# Proiect_TSC_v102.net
KiCad netlist of a schematic drawn in EAGLE
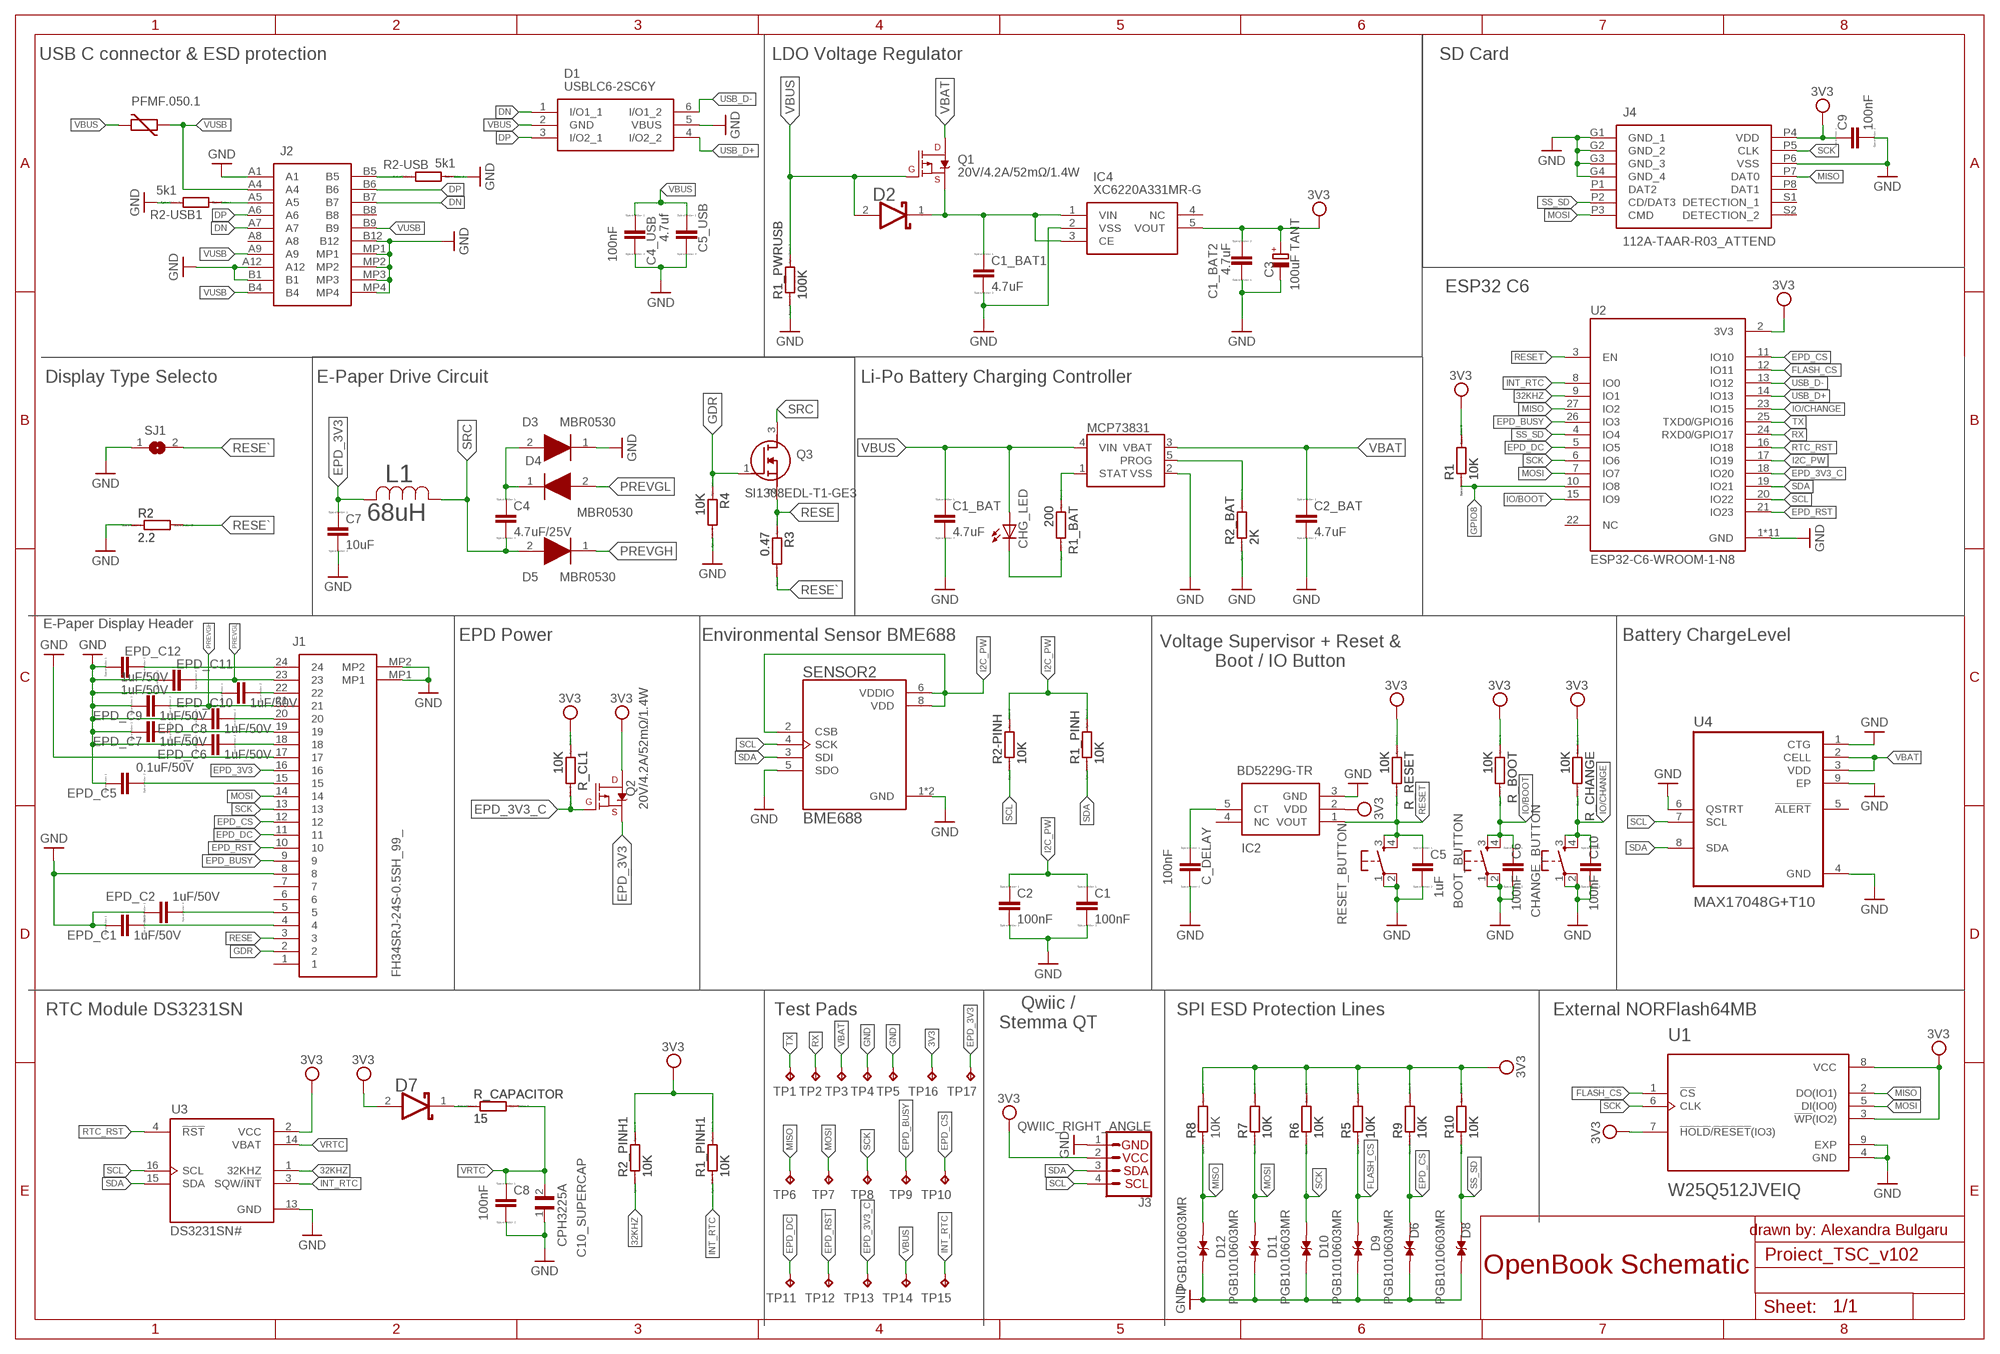
[diagram p0: schematic, sheet 1]

(export (version "E")
  (design (tool "Eeschema 10.0.6"))
  (components
    (comp (ref "BOOT_BUTTON")
      (value "BUTTON_CUSYOMV1")
      (footprint "eagle-import:MYBUTTON")
      (libsource (lib "eagle-import") (part "BUTTON_CUSYOMV1"))
    )
    (comp (ref "C1")
      (value "100nF")
      (footprint "eagle-import:EAGLE-LTSPICE_C0402")
      (libsource (lib "eagle-import") (part "EAGLE-LTSPICE_CC0402"))
    )
    (comp (ref "C1_BAT")
      (value "4.7uF")
      (footprint "eagle-import:EAGLE-LTSPICE_C0402")
      (libsource (lib "eagle-import") (part "EAGLE-LTSPICE_CC0402"))
    )
    (comp (ref "C1_BAT1")
      (value "4.7uF")
      (footprint "eagle-import:EAGLE-LTSPICE_C0402")
      (libsource (lib "eagle-import") (part "EAGLE-LTSPICE_CC0402"))
    )
    (comp (ref "C1_BAT2")
      (value "4.7uF")
      (footprint "eagle-import:EAGLE-LTSPICE_C0402")
      (libsource (lib "eagle-import") (part "EAGLE-LTSPICE_CC0402"))
    )
    (comp (ref "C2")
      (value "100nF")
      (footprint "eagle-import:EAGLE-LTSPICE_C0402")
      (libsource (lib "eagle-import") (part "EAGLE-LTSPICE_CC0402"))
    )
    (comp (ref "C2_BAT")
      (value "4.7uF")
      (footprint "eagle-import:EAGLE-LTSPICE_C0402")
      (libsource (lib "eagle-import") (part "EAGLE-LTSPICE_CC0402"))
    )
    (comp (ref "C3")
      (value "100uF TANT")
      (footprint "eagle-import:RCL_CT3528")
      (libsource (lib "eagle-import") (part "RCL_CPOL-EUCT3528"))
    )
    (comp (ref "C4")
      (value "4.7uF/25V")
      (footprint "eagle-import:EAGLE-LTSPICE_C0402")
      (libsource (lib "eagle-import") (part "EAGLE-LTSPICE_CC0402"))
    )
    (comp (ref "C4_USB")
      (value "100nF")
      (footprint "eagle-import:EAGLE-LTSPICE_C0402")
      (libsource (lib "eagle-import") (part "EAGLE-LTSPICE_CC0402"))
    )
    (comp (ref "C5")
      (value "1uF")
      (footprint "eagle-import:EAGLE-LTSPICE_C0402")
      (libsource (lib "eagle-import") (part "EAGLE-LTSPICE_CC0402"))
    )
    (comp (ref "C5_USB")
      (value "4.7uf")
      (footprint "eagle-import:EAGLE-LTSPICE_C0402")
      (libsource (lib "eagle-import") (part "EAGLE-LTSPICE_CC0402"))
    )
    (comp (ref "C6")
      (value "100nF")
      (footprint "eagle-import:EAGLE-LTSPICE_C0402")
      (libsource (lib "eagle-import") (part "EAGLE-LTSPICE_CC0402"))
    )
    (comp (ref "C7")
      (value "10uF")
      (footprint "eagle-import:EAGLE-LTSPICE_C0402")
      (libsource (lib "eagle-import") (part "EAGLE-LTSPICE_CC0402"))
    )
    (comp (ref "C8")
      (value "100nF")
      (footprint "eagle-import:EAGLE-LTSPICE_C0402")
      (libsource (lib "eagle-import") (part "EAGLE-LTSPICE_CC0402"))
    )
    (comp (ref "C9")
      (value "100nF")
      (footprint "eagle-import:ESP32_WROVER_EAGLE-LTSPICE_C0402")
      (libsource (lib "eagle-import") (part "ESP32_WROVER_EAGLE-LTSPICE_CC0402"))
    )
    (comp (ref "C10")
      (value "100nF")
      (footprint "eagle-import:EAGLE-LTSPICE_C0402")
      (libsource (lib "eagle-import") (part "EAGLE-LTSPICE_CC0402"))
    )
    (comp (ref "C10_SUPERCAP")
      (value "CPH3225A")
      (footprint "eagle-import:CAPCP3225X100N")
      (fields (field (name "MF") "Seiko Instruments"))
      (libsource (lib "eagle-import") (part "CPH3225A"))
    )
    (comp (ref "CHANGE_BUTTON")
      (value "BUTTON_CUSYOMV1")
      (footprint "eagle-import:MYBUTTON")
      (libsource (lib "eagle-import") (part "BUTTON_CUSYOMV1"))
    )
    (comp (ref "CHG_LED")
      (value "ADAFRUIT_LEDCHIP-LED0603")
      (footprint "eagle-import:ADAFRUIT_CHIP-LED0603")
      (libsource (lib "eagle-import") (part "ADAFRUIT_LEDCHIP-LED0603"))
    )
    (comp (ref "C_DELAY")
      (value "100nF")
      (footprint "eagle-import:EAGLE-LTSPICE_C0402")
      (libsource (lib "eagle-import") (part "EAGLE-LTSPICE_CC0402"))
    )
    (comp (ref "D1")
      (value "USBLC6-2SC6Y")
      (footprint "eagle-import:SOT95P280X145-6N")
      (fields (field (name "MF") "STMicroelectronics"))
      (libsource (lib "eagle-import") (part "USBLC6-2SC6Y"))
    )
    (comp (ref "D2")
      (value "ESP32_WROVER_AVX---SD0805S020S1R0_AVX_SD0805S020S1R0_0_0AVX_SD0805S020S1R0_0_0")
      (footprint "eagle-import:ESP32_WROVER_AVX---SD0805S020S1R0_AVX_SD0805S020S1R0_0")
      (fields
        (field (name "DIGIKEY_PART_NUMBER") "478-7800-1-ND")
        (field (name "MF") "AVX")
        (field (name "MOUSER_PART_NUMBER") "581-SD0805S020S1R0")
      )
      (libsource (lib "eagle-import") (part "ESP32_WROVER_AVX---SD0805S020S1R0_AVX_SD0805S020S1R0_0_0AVX_SD0805S020S1R0_0_0"))
    )
    (comp (ref "D3")
      (value "MBR0530")
      (footprint "eagle-import:SOD3716X135N")
      (fields (field (name "MF") "ON Semiconductor"))
      (libsource (lib "eagle-import") (part "MBR0530"))
    )
    (comp (ref "D4")
      (value "MBR0530")
      (footprint "eagle-import:SOD3716X135N")
      (fields (field (name "MF") "ON Semiconductor"))
      (libsource (lib "eagle-import") (part "MBR0530"))
    )
    (comp (ref "D5")
      (value "MBR0530")
      (footprint "eagle-import:SOD3716X135N")
      (fields (field (name "MF") "ON Semiconductor"))
      (libsource (lib "eagle-import") (part "MBR0530"))
    )
    (comp (ref "D6")
      (value "PGB1010603MR")
      (footprint "eagle-import:DIOC1608X36N")
      (fields (field (name "MF") "Littelfuse Inc."))
      (libsource (lib "eagle-import") (part "PGB1010603MR"))
    )
    (comp (ref "D7")
      (value "ESP32_WROVER_AVX---SD0805S020S1R0_AVX_SD0805S020S1R0_0_0AVX_SD0805S020S1R0_0_0")
      (footprint "eagle-import:ESP32_WROVER_AVX---SD0805S020S1R0_AVX_SD0805S020S1R0_0")
      (fields
        (field (name "DIGIKEY_PART_NUMBER") "478-7800-1-ND")
        (field (name "MF") "AVX")
        (field (name "MOUSER_PART_NUMBER") "581-SD0805S020S1R0")
      )
      (libsource (lib "eagle-import") (part "ESP32_WROVER_AVX---SD0805S020S1R0_AVX_SD0805S020S1R0_0_0AVX_SD0805S020S1R0_0_0"))
    )
    (comp (ref "D8")
      (value "PGB1010603MR")
      (footprint "eagle-import:DIOC1608X36N")
      (fields (field (name "MF") "Littelfuse Inc."))
      (libsource (lib "eagle-import") (part "PGB1010603MR"))
    )
    (comp (ref "D9")
      (value "PGB1010603MR")
      (footprint "eagle-import:DIOC1608X36N")
      (fields (field (name "MF") "Littelfuse Inc."))
      (libsource (lib "eagle-import") (part "PGB1010603MR"))
    )
    (comp (ref "D10")
      (value "PGB1010603MR")
      (footprint "eagle-import:DIOC1608X36N")
      (fields (field (name "MF") "Littelfuse Inc."))
      (libsource (lib "eagle-import") (part "PGB1010603MR"))
    )
    (comp (ref "D11")
      (value "PGB1010603MR")
      (footprint "eagle-import:DIOC1608X36N")
      (fields (field (name "MF") "Littelfuse Inc."))
      (libsource (lib "eagle-import") (part "PGB1010603MR"))
    )
    (comp (ref "D12")
      (value "PGB1010603MR")
      (footprint "eagle-import:DIOC1608X36N")
      (fields (field (name "MF") "Littelfuse Inc."))
      (libsource (lib "eagle-import") (part "PGB1010603MR"))
    )
    (comp (ref "EPD_C1")
      (value "1uF/50V")
      (footprint "eagle-import:EAGLE-LTSPICE_C0402")
      (libsource (lib "eagle-import") (part "EAGLE-LTSPICE_CC0402"))
    )
    (comp (ref "EPD_C2")
      (value "1uF/50V")
      (footprint "eagle-import:EAGLE-LTSPICE_C0402")
      (libsource (lib "eagle-import") (part "EAGLE-LTSPICE_CC0402"))
    )
    (comp (ref "EPD_C5")
      (value "0.1uF/50V")
      (footprint "eagle-import:EAGLE-LTSPICE_C0402")
      (libsource (lib "eagle-import") (part "EAGLE-LTSPICE_CC0402"))
    )
    (comp (ref "EPD_C6")
      (value "1uF/50V")
      (footprint "eagle-import:EAGLE-LTSPICE_C0402")
      (libsource (lib "eagle-import") (part "EAGLE-LTSPICE_CC0402"))
    )
    (comp (ref "EPD_C7")
      (value "1uF/50V")
      (footprint "eagle-import:EAGLE-LTSPICE_C0402")
      (libsource (lib "eagle-import") (part "EAGLE-LTSPICE_CC0402"))
    )
    (comp (ref "EPD_C8")
      (value "1uF/50V")
      (footprint "eagle-import:EAGLE-LTSPICE_C0402")
      (libsource (lib "eagle-import") (part "EAGLE-LTSPICE_CC0402"))
    )
    (comp (ref "EPD_C9")
      (value "1uF/50V")
      (footprint "eagle-import:EAGLE-LTSPICE_C0402")
      (libsource (lib "eagle-import") (part "EAGLE-LTSPICE_CC0402"))
    )
    (comp (ref "EPD_C10")
      (value "1uF/50V")
      (footprint "eagle-import:EAGLE-LTSPICE_C0402")
      (libsource (lib "eagle-import") (part "EAGLE-LTSPICE_CC0402"))
    )
    (comp (ref "EPD_C11")
      (value "1uF/50V")
      (footprint "eagle-import:EAGLE-LTSPICE_C0402")
      (libsource (lib "eagle-import") (part "EAGLE-LTSPICE_CC0402"))
    )
    (comp (ref "EPD_C12")
      (value "1uF/50V")
      (footprint "eagle-import:EAGLE-LTSPICE_C0402")
      (libsource (lib "eagle-import") (part "EAGLE-LTSPICE_CC0402"))
    )
    (comp (ref "IC2")
      (value "BD5229G-TR")
      (footprint "eagle-import:SOT95P280X125-5N")
      (fields (field (name "MOUSER_PART_NUMBER") "755-BD5229G-TR"))
      (libsource (lib "eagle-import") (part "BD5229G-TR"))
    )
    (comp (ref "IC4")
      (value "XC6220A331MR-G")
      (footprint "eagle-import:SOT95P280X120-5N")
      (fields (field (name "MOUSER_PART_NUMBER") "865-XC6220A331MR-G"))
      (libsource (lib "eagle-import") (part "XC6220A331MR-G"))
    )
    (comp (ref "J1")
      (value "FH34SRJ-24S-0.5SH_99_")
      (footprint "eagle-import:FH34SRJ24S05SH99")
      (fields
        (field (name "MANUFACTURER_PART_NUMBER") "FH34SRJ-24S-0.5SH(99)")
        (field (name "MOUSER_PART_NUMBER") "798-FH34SRJ24S05SH99")
      )
      (libsource (lib "eagle-import") (part "FH34SRJ-24S-0.5SH_99_"))
    )
    (comp (ref "J2")
      (value "SAMACSYS_PARTS_USB4110-GF-A")
      (footprint "eagle-import:SAMACSYS_PARTS_USB4110GFA")
      (fields
        (field (name "MANUFACTURER_PART_NUMBER") "USB4110-GF-A")
        (field (name "MOUSER_PART_NUMBER") "640-USB4110-GF-A")
      )
      (libsource (lib "eagle-import") (part "SAMACSYS_PARTS_USB4110-GF-A"))
    )
    (comp (ref "J3")
      (value "QWIIC_RIGHT_ANGLE")
      (footprint "eagle-import:JST04_1MM_RA")
      (libsource (lib "eagle-import") (part "QWIIC_CONNECTORJS-1MM"))
    )
    (comp (ref "J4")
      (value "112A-TAAR-R03_ATTEND")
      (footprint "eagle-import:112ATAARR03ATTEND")
      (fields (field (name "MANUFACTURER_PART_NUMBER") "112A-TAAR-R03 ATTEND"))
      (libsource (lib "eagle-import") (part "112A-TAAR-R03_ATTEND"))
    )
    (comp (ref "L1")
      (value "68uH")
      (footprint "eagle-import:IND_4828-WE-TPC_WRE")
      (fields
        (field (name "MANUFACTURER_PART_NUMBER") "744043680")
        (field (name "COPYRIGHT") "Copyright (C) 2024 Ultra Librarian. All rights reserved.")
      )
      (libsource (lib "eagle-import") (part "744043680IND_4828-WE-TPC_WRE"))
    )
    (comp (ref "MCP73831")
      (value "ESP32_WROVER_SPARKFUN-IC-POWER_MCP73831")
      (footprint "eagle-import:ESP32_WROVER_SPARKFUN-IC-POWER_SOT23-5")
      (libsource (lib "eagle-import") (part "ESP32_WROVER_SPARKFUN-IC-POWER_MCP73831"))
    )
    (comp (ref "PFMF.050.1")
      (value "ESP32C6_VARISTORCN1812")
      (footprint "eagle-import:ESP32C6_VARISTOR_CT_CN1812")
      (libsource (lib "eagle-import") (part "ESP32C6_VARISTORCN1812"))
    )
    (comp (ref "Q1")
      (value "20V/4.2A/52mΩ/1.4W")
      (footprint "eagle-import:ESP32_WROVER_SPARKFUN-DISCRETESEMI_SOT23-3")
      (libsource (lib "eagle-import") (part "ESP32_WROVER_SPARKFUN-DISCRETESEMI_MOSFET_PCH-DMG2305UX-7"))
    )
    (comp (ref "Q2")
      (value "20V/4.2A/52mΩ/1.4W")
      (footprint "eagle-import:ESP32_WROVER_SPARKFUN-DISCRETESEMI_SOT23-3")
      (libsource (lib "eagle-import") (part "ESP32_WROVER_SPARKFUN-DISCRETESEMI_MOSFET_PCH-DMG2305UX-7"))
    )
    (comp (ref "Q3")
      (value "SI1308EDL-T1-GE3")
      (footprint "eagle-import:SOT65P210X110-3N")
      (fields (field (name "MF") "Vishay Siliconix"))
      (libsource (lib "eagle-import") (part "SI1308EDL-T1-GE3"))
    )
    (comp (ref "R1")
      (value "10K")
      (footprint "eagle-import:ESP32_WROVER_EAGLE-LTSPICE_R0402")
      (libsource (lib "eagle-import") (part "ESP32_WROVER_EAGLE-LTSPICE_RR0402"))
    )
    (comp (ref "R1_BAT")
      (value "200")
      (footprint "eagle-import:ESP32_WROVER_EAGLE-LTSPICE_R0402")
      (libsource (lib "eagle-import") (part "ESP32_WROVER_EAGLE-LTSPICE_RR0402"))
    )
    (comp (ref "R1_PINH")
      (value "10K")
      (footprint "eagle-import:ESP32_WROVER_EAGLE-LTSPICE_R0402")
      (libsource (lib "eagle-import") (part "ESP32_WROVER_EAGLE-LTSPICE_RR0402"))
    )
    (comp (ref "R1_PINH1")
      (value "10K")
      (footprint "eagle-import:ESP32_WROVER_EAGLE-LTSPICE_R0402")
      (libsource (lib "eagle-import") (part "ESP32_WROVER_EAGLE-LTSPICE_RR0402"))
    )
    (comp (ref "R1_PWRUSB")
      (value "100K")
      (footprint "eagle-import:ESP32_WROVER_EAGLE-LTSPICE_R0402")
      (libsource (lib "eagle-import") (part "ESP32_WROVER_EAGLE-LTSPICE_RR0402"))
    )
    (comp (ref "R2")
      (value "2.2")
      (footprint "eagle-import:ESP32_WROVER_EAGLE-LTSPICE_R0402")
      (libsource (lib "eagle-import") (part "ESP32_WROVER_EAGLE-LTSPICE_RR0402"))
    )
    (comp (ref "R2-PINH")
      (value "10K")
      (footprint "eagle-import:ESP32_WROVER_EAGLE-LTSPICE_R0402")
      (libsource (lib "eagle-import") (part "ESP32_WROVER_EAGLE-LTSPICE_RR0402"))
    )
    (comp (ref "R2-USB")
      (value "5k1")
      (footprint "eagle-import:ESP32_WROVER_EAGLE-LTSPICE_R0402")
      (libsource (lib "eagle-import") (part "ESP32_WROVER_EAGLE-LTSPICE_RR0402"))
    )
    (comp (ref "R2-USB1")
      (value "5k1")
      (footprint "eagle-import:ESP32_WROVER_EAGLE-LTSPICE_R0402")
      (libsource (lib "eagle-import") (part "ESP32_WROVER_EAGLE-LTSPICE_RR0402"))
    )
    (comp (ref "R2_BAT")
      (value "2K")
      (footprint "eagle-import:ESP32_WROVER_EAGLE-LTSPICE_R0402")
      (libsource (lib "eagle-import") (part "ESP32_WROVER_EAGLE-LTSPICE_RR0402"))
    )
    (comp (ref "R2_PINH1")
      (value "10K")
      (footprint "eagle-import:ESP32_WROVER_EAGLE-LTSPICE_R0402")
      (libsource (lib "eagle-import") (part "ESP32_WROVER_EAGLE-LTSPICE_RR0402"))
    )
    (comp (ref "R3")
      (value "0.47")
      (footprint "eagle-import:ESP32_WROVER_EAGLE-LTSPICE_R0402")
      (libsource (lib "eagle-import") (part "ESP32_WROVER_EAGLE-LTSPICE_RR0402"))
    )
    (comp (ref "R4")
      (value "10K")
      (footprint "eagle-import:ESP32_WROVER_EAGLE-LTSPICE_R0402")
      (libsource (lib "eagle-import") (part "ESP32_WROVER_EAGLE-LTSPICE_RR0402"))
    )
    (comp (ref "R5")
      (value "10K")
      (footprint "eagle-import:ESP32_WROVER_EAGLE-LTSPICE_R0402")
      (libsource (lib "eagle-import") (part "ESP32_WROVER_EAGLE-LTSPICE_RR0402"))
    )
    (comp (ref "R6")
      (value "10K")
      (footprint "eagle-import:ESP32_WROVER_EAGLE-LTSPICE_R0402")
      (libsource (lib "eagle-import") (part "ESP32_WROVER_EAGLE-LTSPICE_RR0402"))
    )
    (comp (ref "R7")
      (value "10K")
      (footprint "eagle-import:ESP32_WROVER_EAGLE-LTSPICE_R0402")
      (libsource (lib "eagle-import") (part "ESP32_WROVER_EAGLE-LTSPICE_RR0402"))
    )
    (comp (ref "R8")
      (value "10K")
      (footprint "eagle-import:ESP32_WROVER_EAGLE-LTSPICE_R0402")
      (libsource (lib "eagle-import") (part "ESP32_WROVER_EAGLE-LTSPICE_RR0402"))
    )
    (comp (ref "R9")
      (value "10K")
      (footprint "eagle-import:ESP32_WROVER_EAGLE-LTSPICE_R0402")
      (libsource (lib "eagle-import") (part "ESP32_WROVER_EAGLE-LTSPICE_RR0402"))
    )
    (comp (ref "R10")
      (value "10K")
      (footprint "eagle-import:ESP32_WROVER_EAGLE-LTSPICE_R0402")
      (libsource (lib "eagle-import") (part "ESP32_WROVER_EAGLE-LTSPICE_RR0402"))
    )
    (comp (ref "RESET_BUTTON")
      (value "BUTTON_CUSYOMV1")
      (footprint "eagle-import:MYBUTTON")
      (libsource (lib "eagle-import") (part "BUTTON_CUSYOMV1"))
    )
    (comp (ref "R_BOOT")
      (value "10K")
      (footprint "eagle-import:ESP32_WROVER_EAGLE-LTSPICE_R0402")
      (libsource (lib "eagle-import") (part "ESP32_WROVER_EAGLE-LTSPICE_RR0402"))
    )
    (comp (ref "R_CAPACITOR")
      (value "15")
      (footprint "eagle-import:ESP32_WROVER_EAGLE-LTSPICE_R0402")
      (libsource (lib "eagle-import") (part "ESP32_WROVER_EAGLE-LTSPICE_RR0402"))
    )
    (comp (ref "R_CHANGE")
      (value "10K")
      (footprint "eagle-import:ESP32_WROVER_EAGLE-LTSPICE_R0402")
      (libsource (lib "eagle-import") (part "ESP32_WROVER_EAGLE-LTSPICE_RR0402"))
    )
    (comp (ref "R_CL1")
      (value "10K")
      (footprint "eagle-import:ESP32_WROVER_EAGLE-LTSPICE_R0402")
      (libsource (lib "eagle-import") (part "ESP32_WROVER_EAGLE-LTSPICE_RR0402"))
    )
    (comp (ref "R_RESET")
      (value "10K")
      (footprint "eagle-import:ESP32_WROVER_EAGLE-LTSPICE_R0402")
      (libsource (lib "eagle-import") (part "ESP32_WROVER_EAGLE-LTSPICE_RR0402"))
    )
    (comp (ref "SENSOR2")
      (value "BME688")
      (footprint "eagle-import:ESP32_WROVER_BME680_PSON80P300X300X100-8N")
      (fields (field (name "MF") "Bosch Sensortec") (field (name "MP") "BME680"))
      (libsource (lib "eagle-import") (part "ESP32_WROVER_BME680_BME680"))
    )
    (comp (ref "SJ1") (value "SJ") (footprint "eagle-import:SJ") (libsource (lib "eagle-import") (part "SJ")))
    (comp (ref "TP1")
      (value "TPTP20R")
      (footprint "eagle-import:TP20R")
      (libsource (lib "eagle-import") (part "TPTP20R"))
    )
    (comp (ref "TP2")
      (value "TPTP20R")
      (footprint "eagle-import:TP20R")
      (libsource (lib "eagle-import") (part "TPTP20R"))
    )
    (comp (ref "TP3")
      (value "TPTP20R")
      (footprint "eagle-import:TP20R")
      (libsource (lib "eagle-import") (part "TPTP20R"))
    )
    (comp (ref "TP4")
      (value "TPTP20R")
      (footprint "eagle-import:TP20R")
      (libsource (lib "eagle-import") (part "TPTP20R"))
    )
    (comp (ref "TP5")
      (value "TPTP20R")
      (footprint "eagle-import:TP20R")
      (libsource (lib "eagle-import") (part "TPTP20R"))
    )
    (comp (ref "TP6")
      (value "TPTP20R")
      (footprint "eagle-import:TP20R")
      (libsource (lib "eagle-import") (part "TPTP20R"))
    )
    (comp (ref "TP7")
      (value "TPTP20R")
      (footprint "eagle-import:TP20R")
      (libsource (lib "eagle-import") (part "TPTP20R"))
    )
    (comp (ref "TP8")
      (value "TPTP20R")
      (footprint "eagle-import:TP20R")
      (libsource (lib "eagle-import") (part "TPTP20R"))
    )
    (comp (ref "TP9")
      (value "TPTP20R")
      (footprint "eagle-import:TP20R")
      (libsource (lib "eagle-import") (part "TPTP20R"))
    )
    (comp (ref "TP10")
      (value "TPTP20R")
      (footprint "eagle-import:TP20R")
      (libsource (lib "eagle-import") (part "TPTP20R"))
    )
    (comp (ref "TP11")
      (value "TPTP20R")
      (footprint "eagle-import:TP20R")
      (libsource (lib "eagle-import") (part "TPTP20R"))
    )
    (comp (ref "TP12")
      (value "TPTP20R")
      (footprint "eagle-import:TP20R")
      (libsource (lib "eagle-import") (part "TPTP20R"))
    )
    (comp (ref "TP13")
      (value "TPTP20R")
      (footprint "eagle-import:TP20R")
      (libsource (lib "eagle-import") (part "TPTP20R"))
    )
    (comp (ref "TP14")
      (value "TPTP20R")
      (footprint "eagle-import:TP20R")
      (libsource (lib "eagle-import") (part "TPTP20R"))
    )
    (comp (ref "TP15")
      (value "TPTP20R")
      (footprint "eagle-import:TP20R")
      (libsource (lib "eagle-import") (part "TPTP20R"))
    )
    (comp (ref "TP16")
      (value "TPTP20R")
      (footprint "eagle-import:TP20R")
      (libsource (lib "eagle-import") (part "TPTP20R"))
    )
    (comp (ref "TP17")
      (value "TPTP20R")
      (footprint "eagle-import:TP20R")
      (libsource (lib "eagle-import") (part "TPTP20R"))
    )
    (comp (ref "U1")
      (value "W25Q512JVEIQ")
      (footprint "eagle-import:SON127P600X800X80-9N")
      (fields (field (name "MF") "Winbond Electronics"))
      (libsource (lib "eagle-import") (part "W25Q512JVEIQ"))
    )
    (comp (ref "U2")
      (value "ESP32-C6-WROOM-1-N8")
      (footprint "eagle-import:XCVR_ESP32-C6-WROOM-1-N8")
      (fields (field (name "MF") "Espressif Systems"))
      (libsource (lib "eagle-import") (part "ESP32-C6-WROOM-1-N8"))
    )
    (comp (ref "U3")
      (value "DS3231SN#")
      (footprint "eagle-import:SOIC127P1032X265-16N")
      (fields (field (name "MF") "Analog Devices"))
      (libsource (lib "eagle-import") (part "DS3231SN#"))
    )
    (comp (ref "U4")
      (value "MAX17048G+T10")
      (footprint "eagle-import:SON50P200X200X80-9N")
      (fields (field (name "MF") "Analog Devices"))
      (libsource (lib "eagle-import") (part "MAX17048G+T10"))
    )
  )
  (nets
    (net (code "1") (name "3V3") (class "Default")
      (node (ref "C1_BAT2") (pin "2") (pinfunction "2_2") (pintype "passive"))
      (node (ref "C3") (pin "+") (pinfunction "+_+") (pintype "passive"))
      (node (ref "C9") (pin "1") (pinfunction "1_1") (pintype "passive"))
      (node (ref "D7") (pin "2") (pinfunction "ANODE_2") (pintype "bidirectional"))
      (node (ref "IC2") (pin "2") (pinfunction "VDD_2") (pintype "bidirectional"))
      (node (ref "IC4") (pin "5") (pinfunction "VOUT_5") (pintype "bidirectional"))
      (node (ref "J3") (pin "2") (pinfunction "2_2") (pintype "power_in"))
      (node (ref "J4") (pin "P4") (pinfunction "VDD_P4") (pintype "bidirectional"))
      (node (ref "Q2") (pin "3") (pinfunction "D_3") (pintype "bidirectional"))
      (node (ref "R1") (pin "2") (pinfunction "2_2") (pintype "passive"))
      (node (ref "R10") (pin "2") (pinfunction "2_2") (pintype "passive"))
      (node (ref "R1_PINH1") (pin "2") (pinfunction "2_2") (pintype "passive"))
      (node (ref "R2_PINH1") (pin "2") (pinfunction "2_2") (pintype "passive"))
      (node (ref "R5") (pin "2") (pinfunction "2_2") (pintype "passive"))
      (node (ref "R6") (pin "2") (pinfunction "2_2") (pintype "passive"))
      (node (ref "R7") (pin "2") (pinfunction "2_2") (pintype "passive"))
      (node (ref "R8") (pin "2") (pinfunction "2_2") (pintype "passive"))
      (node (ref "R9") (pin "2") (pinfunction "2_2") (pintype "passive"))
      (node (ref "R_BOOT") (pin "1") (pinfunction "1_1") (pintype "passive"))
      (node (ref "R_CHANGE") (pin "1") (pinfunction "1_1") (pintype "passive"))
      (node (ref "R_CL1") (pin "1") (pinfunction "1_1") (pintype "passive"))
      (node (ref "R_RESET") (pin "1") (pinfunction "1_1") (pintype "passive"))
      (node (ref "TP16") (pin "TP") (pinfunction "TP_TP") (pintype "input"))
      (node (ref "U1") (pin "3") (pinfunction "~{WP}(IO2)_3") (pintype "bidirectional"))
      (node (ref "U1") (pin "7") (pinfunction "~{HOLD}/~{RESET}(IO3)_7") (pintype "bidirectional"))
      (node (ref "U1") (pin "8") (pinfunction "VCC_8") (pintype "power_in"))
      (node (ref "U2") (pin "2") (pinfunction "3V3_2") (pintype "power_in"))
      (node (ref "U3") (pin "2") (pinfunction "VCC_2") (pintype "power_in"))
    )
    (net (code "2") (name "32KHZ") (class "Default")
      (node (ref "R2_PINH1") (pin "1") (pinfunction "1_1") (pintype "passive"))
      (node (ref "U2") (pin "9") (pinfunction "IO1_9") (pintype "bidirectional"))
      (node (ref "U3") (pin "1") (pinfunction "32KHZ_1") (pintype "output"))
    )
    (net (code "3") (name "DN") (class "Default")
      (node (ref "D1") (pin "1") (pinfunction "I/O1_1_1") (pintype "bidirectional"))
      (node (ref "J2") (pin "A7") (pinfunction "A7_A7") (pintype "bidirectional"))
      (node (ref "J2") (pin "B7") (pinfunction "B7_B7") (pintype "bidirectional"))
    )
    (net (code "4") (name "DP") (class "Default")
      (node (ref "D1") (pin "3") (pinfunction "I/O2_1_3") (pintype "bidirectional"))
      (node (ref "J2") (pin "A6") (pinfunction "A6_A6") (pintype "bidirectional"))
      (node (ref "J2") (pin "B6") (pinfunction "B6_B6") (pintype "bidirectional"))
    )
    (net (code "5") (name "EPD_3V3") (class "Default")
      (node (ref "C7") (pin "1") (pinfunction "1_1") (pintype "passive"))
      (node (ref "J1") (pin "16") (pinfunction "16_16") (pintype "bidirectional"))
      (node (ref "L1") (pin "2") (pinfunction "2_2") (pintype "passive"))
      (node (ref "Q2") (pin "2") (pinfunction "S_2") (pintype "bidirectional"))
      (node (ref "TP17") (pin "TP") (pinfunction "TP_TP") (pintype "input"))
    )
    (net (code "6") (name "EPD_3V3_C") (class "Default")
      (node (ref "Q2") (pin "1") (pinfunction "G_1") (pintype "bidirectional"))
      (node (ref "R_CL1") (pin "2") (pinfunction "2_2") (pintype "passive"))
      (node (ref "TP13") (pin "TP") (pinfunction "TP_TP") (pintype "input"))
      (node (ref "U2") (pin "18") (pinfunction "IO20_18") (pintype "bidirectional"))
    )
    (net (code "7") (name "EPD_BUSY") (class "Default")
      (node (ref "J1") (pin "9") (pinfunction "9_9") (pintype "bidirectional"))
      (node (ref "TP9") (pin "TP") (pinfunction "TP_TP") (pintype "input"))
      (node (ref "U2") (pin "26") (pinfunction "IO3_26") (pintype "bidirectional"))
    )
    (net (code "8") (name "EPD_CS") (class "Default")
      (node (ref "D6") (pin "1") (pinfunction "1_1") (pintype "passive"))
      (node (ref "J1") (pin "12") (pinfunction "12_12") (pintype "bidirectional"))
      (node (ref "R9") (pin "1") (pinfunction "1_1") (pintype "passive"))
      (node (ref "TP10") (pin "TP") (pinfunction "TP_TP") (pintype "input"))
      (node (ref "U2") (pin "11") (pinfunction "IO10_11") (pintype "bidirectional"))
    )
    (net (code "9") (name "EPD_DC") (class "Default")
      (node (ref "J1") (pin "11") (pinfunction "11_11") (pintype "bidirectional"))
      (node (ref "TP11") (pin "TP") (pinfunction "TP_TP") (pintype "input"))
      (node (ref "U2") (pin "5") (pinfunction "IO5_5") (pintype "bidirectional"))
    )
    (net (code "10") (name "EPD_RST") (class "Default")
      (node (ref "J1") (pin "10") (pinfunction "10_10") (pintype "bidirectional"))
      (node (ref "TP12") (pin "TP") (pinfunction "TP_TP") (pintype "input"))
      (node (ref "U2") (pin "21") (pinfunction "IO23_21") (pintype "bidirectional"))
    )
    (net (code "11") (name "FLASH_CS") (class "Default")
      (node (ref "D9") (pin "1") (pinfunction "1_1") (pintype "passive"))
      (node (ref "R5") (pin "1") (pinfunction "1_1") (pintype "passive"))
      (node (ref "U1") (pin "1") (pinfunction "~{CS}_1") (pintype "input"))
      (node (ref "U2") (pin "12") (pinfunction "IO11_12") (pintype "bidirectional"))
    )
    (net (code "12") (name "GDR") (class "Default")
      (node (ref "J1") (pin "2") (pinfunction "2_2") (pintype "bidirectional"))
      (node (ref "Q3") (pin "1") (pinfunction "G_1") (pintype "bidirectional"))
      (node (ref "R4") (pin "1") (pinfunction "1_1") (pintype "passive"))
    )
    (net (code "13") (name "GND") (class "Default")
      (node (ref "BOOT_BUTTON") (pin "1") (pinfunction "1_1") (pintype "passive"))
      (node (ref "BOOT_BUTTON") (pin "2") (pinfunction "2_2") (pintype "passive"))
      (node (ref "C1") (pin "2") (pinfunction "2_2") (pintype "passive"))
      (node (ref "C10") (pin "2") (pinfunction "2_2") (pintype "passive"))
      (node (ref "C10_SUPERCAP") (pin "1") (pinfunction "1_1") (pintype "passive"))
      (node (ref "C1_BAT") (pin "2") (pinfunction "2_2") (pintype "passive"))
      (node (ref "C1_BAT1") (pin "2") (pinfunction "2_2") (pintype "passive"))
      (node (ref "C1_BAT2") (pin "1") (pinfunction "1_1") (pintype "passive"))
      (node (ref "C2") (pin "2") (pinfunction "2_2") (pintype "passive"))
      (node (ref "C2_BAT") (pin "2") (pinfunction "2_2") (pintype "passive"))
      (node (ref "C3") (pin "-") (pinfunction "-_-") (pintype "passive"))
      (node (ref "C4_USB") (pin "2") (pinfunction "2_2") (pintype "passive"))
      (node (ref "C5") (pin "2") (pinfunction "2_2") (pintype "passive"))
      (node (ref "C5_USB") (pin "2") (pinfunction "2_2") (pintype "passive"))
      (node (ref "C6") (pin "2") (pinfunction "2_2") (pintype "passive"))
      (node (ref "C7") (pin "2") (pinfunction "2_2") (pintype "passive"))
      (node (ref "C8") (pin "2") (pinfunction "2_2") (pintype "passive"))
      (node (ref "C9") (pin "2") (pinfunction "2_2") (pintype "passive"))
      (node (ref "CHANGE_BUTTON") (pin "1") (pinfunction "1_1") (pintype "passive"))
      (node (ref "CHANGE_BUTTON") (pin "2") (pinfunction "2_2") (pintype "passive"))
      (node (ref "C_DELAY") (pin "2") (pinfunction "2_2") (pintype "passive"))
      (node (ref "D1") (pin "5") (pinfunction "VBUS_5") (pintype "bidirectional"))
      (node (ref "D10") (pin "2") (pinfunction "2_2") (pintype "passive"))
      (node (ref "D11") (pin "2") (pinfunction "2_2") (pintype "passive"))
      (node (ref "D12") (pin "2") (pinfunction "2_2") (pintype "passive"))
      (node (ref "D3") (pin "1") (pinfunction "K_1") (pintype "bidirectional"))
      (node (ref "D6") (pin "2") (pinfunction "2_2") (pintype "passive"))
      (node (ref "D8") (pin "2") (pinfunction "2_2") (pintype "passive"))
      (node (ref "D9") (pin "2") (pinfunction "2_2") (pintype "passive"))
      (node (ref "EPD_C1") (pin "1") (pinfunction "1_1") (pintype "passive"))
      (node (ref "EPD_C10") (pin "1") (pinfunction "1_1") (pintype "passive"))
      (node (ref "EPD_C11") (pin "1") (pinfunction "1_1") (pintype "passive"))
      (node (ref "EPD_C12") (pin "1") (pinfunction "1_1") (pintype "passive"))
      (node (ref "EPD_C2") (pin "1") (pinfunction "1_1") (pintype "passive"))
      (node (ref "EPD_C5") (pin "1") (pinfunction "1_1") (pintype "passive"))
      (node (ref "EPD_C6") (pin "1") (pinfunction "1_1") (pintype "passive"))
      (node (ref "EPD_C7") (pin "1") (pinfunction "1_1") (pintype "passive"))
      (node (ref "EPD_C8") (pin "1") (pinfunction "1_1") (pintype "passive"))
      (node (ref "EPD_C9") (pin "1") (pinfunction "1_1") (pintype "passive"))
      (node (ref "IC2") (pin "3") (pinfunction "GND_3") (pintype "bidirectional"))
      (node (ref "IC4") (pin "2") (pinfunction "VSS_2") (pintype "bidirectional"))
      (node (ref "J1") (pin "17") (pinfunction "17_17") (pintype "bidirectional"))
      (node (ref "J1") (pin "8") (pinfunction "8_8") (pintype "bidirectional"))
      (node (ref "J1") (pin "MP1") (pinfunction "MP1_MP1") (pintype "bidirectional"))
      (node (ref "J1") (pin "MP2") (pinfunction "MP2_MP2") (pintype "bidirectional"))
      (node (ref "J2") (pin "A1") (pinfunction "A1_A1") (pintype "bidirectional"))
      (node (ref "J2") (pin "A12") (pinfunction "A12_A12") (pintype "bidirectional"))
      (node (ref "J2") (pin "B1") (pinfunction "B1_B1") (pintype "bidirectional"))
      (node (ref "J2") (pin "B12") (pinfunction "B12_B12") (pintype "bidirectional"))
      (node (ref "J2") (pin "MP1") (pinfunction "MP1_MP1") (pintype "bidirectional"))
      (node (ref "J2") (pin "MP2") (pinfunction "MP2_MP2") (pintype "bidirectional"))
      (node (ref "J2") (pin "MP3") (pinfunction "MP3_MP3") (pintype "bidirectional"))
      (node (ref "J2") (pin "MP4") (pinfunction "MP4_MP4") (pintype "bidirectional"))
      (node (ref "J3") (pin "1") (pinfunction "1_1") (pintype "power_in"))
      (node (ref "J4") (pin "G1") (pinfunction "GND_1_G1") (pintype "bidirectional"))
      (node (ref "J4") (pin "G2") (pinfunction "GND_2_G2") (pintype "bidirectional"))
      (node (ref "J4") (pin "G3") (pinfunction "GND_3_G3") (pintype "bidirectional"))
      (node (ref "J4") (pin "G4") (pinfunction "GND_4_G4") (pintype "bidirectional"))
      (node (ref "J4") (pin "P6") (pinfunction "VSS_P6") (pintype "bidirectional"))
      (node (ref "MCP73831") (pin "2") (pinfunction "VSS_2") (pintype "power_in"))
      (node (ref "R1_PWRUSB") (pin "1") (pinfunction "1_1") (pintype "passive"))
      (node (ref "R2") (pin "1") (pinfunction "1_1") (pintype "passive"))
      (node (ref "R2-USB") (pin "2") (pinfunction "2_2") (pintype "passive"))
      (node (ref "R2-USB1") (pin "2") (pinfunction "2_2") (pintype "passive"))
      (node (ref "R2_BAT") (pin "1") (pinfunction "1_1") (pintype "passive"))
      (node (ref "R4") (pin "2") (pinfunction "2_2") (pintype "passive"))
      (node (ref "RESET_BUTTON") (pin "1") (pinfunction "1_1") (pintype "passive"))
      (node (ref "RESET_BUTTON") (pin "2") (pinfunction "2_2") (pintype "passive"))
      (node (ref "SENSOR2") (pin "1") (pinfunction "GND_1") (pintype "power_in"))
      (node (ref "SENSOR2") (pin "5") (pinfunction "SDO_5") (pintype "bidirectional"))
      (node (ref "SENSOR2") (pin "7") (pinfunction "GND_7") (pintype "power_in"))
      (node (ref "SJ1") (pin "1") (pinfunction "1_1") (pintype "passive"))
      (node (ref "TP4") (pin "TP") (pinfunction "TP_TP") (pintype "input"))
      (node (ref "TP5") (pin "TP") (pinfunction "TP_TP") (pintype "input"))
      (node (ref "U1") (pin "4") (pinfunction "GND_4") (pintype "power_in"))
      (node (ref "U1") (pin "9") (pinfunction "EXP_9") (pintype "passive"))
      (node (ref "U2") (pin "1") (pinfunction "GND_1") (pintype "power_in"))
      (node (ref "U2") (pin "28") (pinfunction "GND_28") (pintype "power_in"))
      (node (ref "U2") (pin "29_1") (pinfunction "GND_29_1") (pintype "power_in"))
      (node (ref "U2") (pin "29_2") (pinfunction "GND_29_2") (pintype "power_in"))
      (node (ref "U2") (pin "29_3") (pinfunction "GND_29_3") (pintype "power_in"))
      (node (ref "U2") (pin "29_4") (pinfunction "GND_29_4") (pintype "power_in"))
      (node (ref "U2") (pin "29_5") (pinfunction "GND_29_5") (pintype "power_in"))
      (node (ref "U2") (pin "29_6") (pinfunction "GND_29_6") (pintype "power_in"))
      (node (ref "U2") (pin "29_7") (pinfunction "GND_29_7") (pintype "power_in"))
      (node (ref "U2") (pin "29_8") (pinfunction "GND_29_8") (pintype "power_in"))
      (node (ref "U2") (pin "29_9") (pinfunction "GND_29_9") (pintype "power_in"))
      (node (ref "U3") (pin "13") (pinfunction "GND_13") (pintype "power_in"))
      (node (ref "U4") (pin "1") (pinfunction "CTG_1") (pintype "power_in"))
      (node (ref "U4") (pin "4") (pinfunction "GND_4") (pintype "power_in"))
      (node (ref "U4") (pin "6") (pinfunction "QSTRT_6") (pintype "input"))
      (node (ref "U4") (pin "9") (pinfunction "EP_9") (pintype "power_in"))
    )
    (net (code "14") (name "GPIO8") (class "Default")
      (node (ref "R1") (pin "1") (pinfunction "1_1") (pintype "passive"))
      (node (ref "U2") (pin "10") (pinfunction "IO8_10") (pintype "bidirectional"))
    )
    (net (code "15") (name "I2C_PW") (class "Default")
      (node (ref "C1") (pin "1") (pinfunction "1_1") (pintype "passive"))
      (node (ref "C2") (pin "1") (pinfunction "1_1") (pintype "passive"))
      (node (ref "R1_PINH") (pin "2") (pinfunction "2_2") (pintype "passive"))
      (node (ref "R2-PINH") (pin "2") (pinfunction "2_2") (pintype "passive"))
      (node (ref "SENSOR2") (pin "2") (pinfunction "CSB_2") (pintype "input"))
      (node (ref "SENSOR2") (pin "6") (pinfunction "VDDIO_6") (pintype "power_in"))
      (node (ref "SENSOR2") (pin "8") (pinfunction "VDD_8") (pintype "power_in"))
      (node (ref "U2") (pin "17") (pinfunction "IO19_17") (pintype "bidirectional"))
    )
    (net (code "16") (name "INT_RTC") (class "Default")
      (node (ref "R1_PINH1") (pin "1") (pinfunction "1_1") (pintype "passive"))
      (node (ref "TP15") (pin "TP") (pinfunction "TP_TP") (pintype "input"))
      (node (ref "U2") (pin "8") (pinfunction "IO0_8") (pintype "bidirectional"))
      (node (ref "U3") (pin "3") (pinfunction "SQW/~{INT}_3") (pintype "output"))
    )
    (net (code "17") (name "IO{slash}BOOT") (class "Default")
      (node (ref "BOOT_BUTTON") (pin "3") (pinfunction "3_3") (pintype "passive"))
      (node (ref "BOOT_BUTTON") (pin "4") (pinfunction "4_4") (pintype "passive"))
      (node (ref "C6") (pin "1") (pinfunction "1_1") (pintype "passive"))
      (node (ref "R_BOOT") (pin "2") (pinfunction "2_2") (pintype "passive"))
      (node (ref "U2") (pin "15") (pinfunction "IO9_15") (pintype "bidirectional"))
    )
    (net (code "18") (name "IO{slash}CHANGE") (class "Default")
      (node (ref "C10") (pin "1") (pinfunction "1_1") (pintype "passive"))
      (node (ref "CHANGE_BUTTON") (pin "3") (pinfunction "3_3") (pintype "passive"))
      (node (ref "CHANGE_BUTTON") (pin "4") (pinfunction "4_4") (pintype "passive"))
      (node (ref "R_CHANGE") (pin "2") (pinfunction "2_2") (pintype "passive"))
      (node (ref "U2") (pin "23") (pinfunction "IO15_23") (pintype "bidirectional"))
    )
    (net (code "19") (name "MISO") (class "Default")
      (node (ref "D12") (pin "1") (pinfunction "1_1") (pintype "passive"))
      (node (ref "J4") (pin "P7") (pinfunction "DAT0_P7") (pintype "bidirectional"))
      (node (ref "R8") (pin "1") (pinfunction "1_1") (pintype "passive"))
      (node (ref "TP6") (pin "TP") (pinfunction "TP_TP") (pintype "input"))
      (node (ref "U1") (pin "2") (pinfunction "DO(IO1)_2") (pintype "bidirectional"))
      (node (ref "U2") (pin "27") (pinfunction "IO2_27") (pintype "bidirectional"))
    )
    (net (code "20") (name "MOSI") (class "Default")
      (node (ref "D11") (pin "1") (pinfunction "1_1") (pintype "passive"))
      (node (ref "J1") (pin "14") (pinfunction "14_14") (pintype "bidirectional"))
      (node (ref "J4") (pin "P3") (pinfunction "CMD_P3") (pintype "bidirectional"))
      (node (ref "R7") (pin "1") (pinfunction "1_1") (pintype "passive"))
      (node (ref "TP7") (pin "TP") (pinfunction "TP_TP") (pintype "input"))
      (node (ref "U1") (pin "5") (pinfunction "DI(IO0)_5") (pintype "bidirectional"))
      (node (ref "U2") (pin "7") (pinfunction "IO7_7") (pintype "bidirectional"))
    )
    (net (code "21") (name "Net-(CHG_LED-PadC)") (class "Default")
      (node (ref "CHG_LED") (pin "C") (pinfunction "C_C") (pintype "passive"))
      (node (ref "R1_BAT") (pin "2") (pinfunction "2_2") (pintype "passive"))
    )
    (net (code "22") (name "Net-(D2-CATHODE)") (class "Default")
      (node (ref "C1_BAT1") (pin "1") (pinfunction "1_1") (pintype "passive"))
      (node (ref "D2") (pin "1") (pinfunction "CATHODE_1") (pintype "bidirectional"))
      (node (ref "IC4") (pin "1") (pinfunction "VIN_1") (pintype "bidirectional"))
      (node (ref "IC4") (pin "3") (pinfunction "CE_3") (pintype "bidirectional"))
      (node (ref "Q1") (pin "2") (pinfunction "S_2") (pintype "bidirectional"))
    )
    (net (code "23") (name "Net-(D3-A)") (class "Default")
      (node (ref "C4") (pin "1") (pinfunction "1_1") (pintype "passive"))
      (node (ref "D3") (pin "2") (pinfunction "A_2") (pintype "bidirectional"))
      (node (ref "D4") (pin "1") (pinfunction "K_1") (pintype "bidirectional"))
    )
    (net (code "24") (name "Net-(D7-CATHODE)") (class "Default")
      (node (ref "D7") (pin "1") (pinfunction "CATHODE_1") (pintype "bidirectional"))
      (node (ref "R_CAPACITOR") (pin "1") (pinfunction "1_1") (pintype "passive"))
    )
    (net (code "25") (name "Net-(EPD_C1-Pad2)") (class "Default")
      (node (ref "EPD_C1") (pin "2") (pinfunction "2_2") (pintype "passive"))
      (node (ref "J1") (pin "4") (pinfunction "4_4") (pintype "bidirectional"))
    )
    (net (code "26") (name "Net-(EPD_C2-Pad2)") (class "Default")
      (node (ref "EPD_C2") (pin "2") (pinfunction "2_2") (pintype "passive"))
      (node (ref "J1") (pin "5") (pinfunction "5_5") (pintype "bidirectional"))
    )
    (net (code "27") (name "Net-(EPD_C5-Pad2)") (class "Default")
      (node (ref "EPD_C5") (pin "2") (pinfunction "2_2") (pintype "passive"))
      (node (ref "J1") (pin "15") (pinfunction "15_15") (pintype "bidirectional"))
    )
    (net (code "28") (name "Net-(EPD_C6-Pad2)") (class "Default")
      (node (ref "EPD_C6") (pin "2") (pinfunction "2_2") (pintype "passive"))
      (node (ref "J1") (pin "18") (pinfunction "18_18") (pintype "bidirectional"))
    )
    (net (code "29") (name "Net-(EPD_C7-Pad2)") (class "Default")
      (node (ref "EPD_C7") (pin "2") (pinfunction "2_2") (pintype "passive"))
      (node (ref "J1") (pin "19") (pinfunction "19_19") (pintype "bidirectional"))
    )
    (net (code "30") (name "Net-(EPD_C8-Pad2)") (class "Default")
      (node (ref "EPD_C8") (pin "2") (pinfunction "2_2") (pintype "passive"))
      (node (ref "J1") (pin "20") (pinfunction "20_20") (pintype "bidirectional"))
    )
    (net (code "31") (name "Net-(EPD_C10-Pad2)") (class "Default")
      (node (ref "EPD_C10") (pin "2") (pinfunction "2_2") (pintype "passive"))
      (node (ref "J1") (pin "22") (pinfunction "22_22") (pintype "bidirectional"))
    )
    (net (code "32") (name "Net-(EPD_C12-Pad2)") (class "Default")
      (node (ref "EPD_C12") (pin "2") (pinfunction "2_2") (pintype "passive"))
      (node (ref "J1") (pin "24") (pinfunction "24_24") (pintype "bidirectional"))
    )
    (net (code "33") (name "Net-(IC2-CT)") (class "Default")
      (node (ref "C_DELAY") (pin "1") (pinfunction "1_1") (pintype "passive"))
      (node (ref "IC2") (pin "5") (pinfunction "CT_5") (pintype "bidirectional"))
    )
    (net (code "34") (name "Net-(J2-PadA5)") (class "Default")
      (node (ref "J2") (pin "A5") (pinfunction "A5_A5") (pintype "bidirectional"))
      (node (ref "R2-USB1") (pin "1") (pinfunction "1_1") (pintype "passive"))
    )
    (net (code "35") (name "Net-(J2-PadB5)") (class "Default")
      (node (ref "J2") (pin "B5") (pinfunction "B5_B5") (pintype "bidirectional"))
      (node (ref "R2-USB") (pin "1") (pinfunction "1_1") (pintype "passive"))
    )
    (net (code "36") (name "Net-(MCP73831-PROG)") (class "Default")
      (node (ref "MCP73831") (pin "5") (pinfunction "PROG_5") (pintype "input"))
      (node (ref "R2_BAT") (pin "2") (pinfunction "2_2") (pintype "passive"))
    )
    (net (code "37") (name "Net-(MCP73831-STAT)") (class "Default")
      (node (ref "MCP73831") (pin "1") (pinfunction "STAT_1") (pintype "output"))
      (node (ref "R1_BAT") (pin "1") (pinfunction "1_1") (pintype "passive"))
    )
    (net (code "38") (name "PREVGH") (class "Default")
      (node (ref "D5") (pin "1") (pinfunction "K_1") (pintype "bidirectional"))
      (node (ref "EPD_C9") (pin "2") (pinfunction "2_2") (pintype "passive"))
      (node (ref "J1") (pin "21") (pinfunction "21_21") (pintype "bidirectional"))
    )
    (net (code "39") (name "PREVGL") (class "Default")
      (node (ref "D4") (pin "2") (pinfunction "A_2") (pintype "bidirectional"))
      (node (ref "EPD_C11") (pin "2") (pinfunction "2_2") (pintype "passive"))
      (node (ref "J1") (pin "23") (pinfunction "23_23") (pintype "bidirectional"))
    )
    (net (code "40") (name "RESE") (class "Default")
      (node (ref "J1") (pin "3") (pinfunction "3_3") (pintype "bidirectional"))
      (node (ref "Q3") (pin "2") (pinfunction "S_2") (pintype "bidirectional"))
      (node (ref "R3") (pin "1") (pinfunction "1_1") (pintype "passive"))
    )
    (net (code "41") (name "RESET") (class "Default")
      (node (ref "C5") (pin "1") (pinfunction "1_1") (pintype "passive"))
      (node (ref "IC2") (pin "1") (pinfunction "VOUT_1") (pintype "bidirectional"))
      (node (ref "RESET_BUTTON") (pin "3") (pinfunction "3_3") (pintype "passive"))
      (node (ref "RESET_BUTTON") (pin "4") (pinfunction "4_4") (pintype "passive"))
      (node (ref "R_RESET") (pin "2") (pinfunction "2_2") (pintype "passive"))
      (node (ref "U2") (pin "3") (pinfunction "EN_3") (pintype "input"))
    )
    (net (code "42") (name "RESE`") (class "Default")
      (node (ref "R2") (pin "2") (pinfunction "2_2") (pintype "passive"))
      (node (ref "R3") (pin "2") (pinfunction "2_2") (pintype "passive"))
      (node (ref "SJ1") (pin "2") (pinfunction "2_2") (pintype "passive"))
    )
    (net (code "43") (name "RTC_RST") (class "Default")
      (node (ref "U2") (pin "16") (pinfunction "IO18_16") (pintype "bidirectional"))
      (node (ref "U3") (pin "4") (pinfunction "~{RST}_4") (pintype "input"))
    )
    (net (code "44") (name "RX") (class "Default")
      (node (ref "TP2") (pin "TP") (pinfunction "TP_TP") (pintype "input"))
      (node (ref "U2") (pin "24") (pinfunction "RXD0/GPIO17_24") (pintype "bidirectional"))
    )
    (net (code "45") (name "SCK") (class "Default")
      (node (ref "D10") (pin "1") (pinfunction "1_1") (pintype "passive"))
      (node (ref "J1") (pin "13") (pinfunction "13_13") (pintype "bidirectional"))
      (node (ref "J4") (pin "P5") (pinfunction "CLK_P5") (pintype "bidirectional"))
      (node (ref "R6") (pin "1") (pinfunction "1_1") (pintype "passive"))
      (node (ref "TP8") (pin "TP") (pinfunction "TP_TP") (pintype "input"))
      (node (ref "U1") (pin "6") (pinfunction "CLK_6") (pintype "input"))
      (node (ref "U2") (pin "6") (pinfunction "IO6_6") (pintype "bidirectional"))
    )
    (net (code "46") (name "SCL") (class "Default")
      (node (ref "J3") (pin "4") (pinfunction "4_4") (pintype "passive"))
      (node (ref "R2-PINH") (pin "1") (pinfunction "1_1") (pintype "passive"))
      (node (ref "SENSOR2") (pin "4") (pinfunction "SCK_4") (pintype "input"))
      (node (ref "U2") (pin "20") (pinfunction "IO22_20") (pintype "bidirectional"))
      (node (ref "U3") (pin "16") (pinfunction "SCL_16") (pintype "input"))
      (node (ref "U4") (pin "7") (pinfunction "SCL_7") (pintype "input"))
    )
    (net (code "47") (name "SDA") (class "Default")
      (node (ref "J3") (pin "3") (pinfunction "3_3") (pintype "passive"))
      (node (ref "R1_PINH") (pin "1") (pinfunction "1_1") (pintype "passive"))
      (node (ref "SENSOR2") (pin "3") (pinfunction "SDI_3") (pintype "bidirectional"))
      (node (ref "U2") (pin "19") (pinfunction "IO21_19") (pintype "bidirectional"))
      (node (ref "U3") (pin "15") (pinfunction "SDA_15") (pintype "bidirectional"))
      (node (ref "U4") (pin "8") (pinfunction "SDA_8") (pintype "bidirectional"))
    )
    (net (code "48") (name "SRC") (class "Default")
      (node (ref "C4") (pin "2") (pinfunction "2_2") (pintype "passive"))
      (node (ref "D5") (pin "2") (pinfunction "A_2") (pintype "bidirectional"))
      (node (ref "L1") (pin "1") (pinfunction "1_1") (pintype "passive"))
      (node (ref "Q3") (pin "3") (pinfunction "D_3") (pintype "bidirectional"))
    )
    (net (code "49") (name "SS_SD") (class "Default")
      (node (ref "D8") (pin "1") (pinfunction "1_1") (pintype "passive"))
      (node (ref "J4") (pin "P2") (pinfunction "CD/DAT3_P2") (pintype "bidirectional"))
      (node (ref "R10") (pin "1") (pinfunction "1_1") (pintype "passive"))
      (node (ref "U2") (pin "4") (pinfunction "IO4_4") (pintype "bidirectional"))
    )
    (net (code "50") (name "TX") (class "Default")
      (node (ref "TP1") (pin "TP") (pinfunction "TP_TP") (pintype "input"))
      (node (ref "U2") (pin "25") (pinfunction "TXD0/GPIO16_25") (pintype "bidirectional"))
    )
    (net (code "51") (name "USB_D+") (class "Default")
      (node (ref "D1") (pin "4") (pinfunction "I/O2_2_4") (pintype "bidirectional"))
      (node (ref "U2") (pin "14") (pinfunction "IO13_14") (pintype "bidirectional"))
    )
    (net (code "52") (name "USB_D-") (class "Default")
      (node (ref "D1") (pin "6") (pinfunction "I/O1_2_6") (pintype "bidirectional"))
      (node (ref "U2") (pin "13") (pinfunction "IO12_13") (pintype "bidirectional"))
    )
    (net (code "53") (name "VBAT") (class "Default")
      (node (ref "C2_BAT") (pin "1") (pinfunction "1_1") (pintype "passive"))
      (node (ref "MCP73831") (pin "3") (pinfunction "VBAT_3") (pintype "power_in"))
      (node (ref "Q1") (pin "3") (pinfunction "D_3") (pintype "bidirectional"))
      (node (ref "TP3") (pin "TP") (pinfunction "TP_TP") (pintype "input"))
      (node (ref "U4") (pin "2") (pinfunction "CELL_2") (pintype "power_in"))
      (node (ref "U4") (pin "3") (pinfunction "VDD_3") (pintype "power_in"))
    )
    (net (code "54") (name "VBUS") (class "Default")
      (node (ref "C1_BAT") (pin "1") (pinfunction "1_1") (pintype "passive"))
      (node (ref "C4_USB") (pin "1") (pinfunction "1_1") (pintype "passive"))
      (node (ref "C5_USB") (pin "1") (pinfunction "1_1") (pintype "passive"))
      (node (ref "CHG_LED") (pin "A") (pinfunction "A_A") (pintype "passive"))
      (node (ref "D1") (pin "2") (pinfunction "GND_2") (pintype "bidirectional"))
      (node (ref "D2") (pin "2") (pinfunction "ANODE_2") (pintype "bidirectional"))
      (node (ref "MCP73831") (pin "4") (pinfunction "VIN_4") (pintype "power_in"))
      (node (ref "PFMF.050.1") (pin "2") (pinfunction "2_2") (pintype "passive"))
      (node (ref "Q1") (pin "1") (pinfunction "G_1") (pintype "bidirectional"))
      (node (ref "R1_PWRUSB") (pin "2") (pinfunction "2_2") (pintype "passive"))
      (node (ref "TP14") (pin "TP") (pinfunction "TP_TP") (pintype "input"))
    )
    (net (code "55") (name "VRTC") (class "Default")
      (node (ref "C10_SUPERCAP") (pin "2") (pinfunction "2_2") (pintype "passive"))
      (node (ref "C8") (pin "1") (pinfunction "1_1") (pintype "passive"))
      (node (ref "R_CAPACITOR") (pin "2") (pinfunction "2_2") (pintype "passive"))
      (node (ref "U3") (pin "14") (pinfunction "VBAT_14") (pintype "power_in"))
    )
    (net (code "56") (name "VUSB") (class "Default")
      (node (ref "J2") (pin "A4") (pinfunction "A4_A4") (pintype "bidirectional"))
      (node (ref "J2") (pin "A9") (pinfunction "A9_A9") (pintype "bidirectional"))
      (node (ref "J2") (pin "B4") (pinfunction "B4_B4") (pintype "bidirectional"))
      (node (ref "J2") (pin "B9") (pinfunction "B9_B9") (pintype "bidirectional"))
      (node (ref "PFMF.050.1") (pin "1") (pinfunction "1_1") (pintype "passive"))
    )
    (net (code "57") (name "unconnected-(IC2-NC-Pad4)") (class "Default")
      (node (ref "IC2") (pin "4") (pinfunction "NC_4") (pintype "no_connect"))
    )
    (net (code "58") (name "unconnected-(IC4-NC-Pad4)") (class "Default")
      (node (ref "IC4") (pin "4") (pinfunction "NC_4") (pintype "no_connect"))
    )
    (net (code "59") (name "unconnected-(J1-Pad1)") (class "Default")
      (node (ref "J1") (pin "1") (pinfunction "1_1") (pintype "bidirectional"))
    )
    (net (code "60") (name "unconnected-(J1-Pad6)") (class "Default")
      (node (ref "J1") (pin "6") (pinfunction "6_6") (pintype "bidirectional"))
    )
    (net (code "61") (name "unconnected-(J1-Pad7)") (class "Default")
      (node (ref "J1") (pin "7") (pinfunction "7_7") (pintype "bidirectional"))
    )
    (net (code "62") (name "unconnected-(J2-PadA8)") (class "Default")
      (node (ref "J2") (pin "A8") (pinfunction "A8_A8") (pintype "bidirectional"))
    )
    (net (code "63") (name "unconnected-(J2-PadB8)") (class "Default")
      (node (ref "J2") (pin "B8") (pinfunction "B8_B8") (pintype "bidirectional"))
    )
    (net (code "64") (name "unconnected-(J4-DAT1-PadP8)") (class "Default")
      (node (ref "J4") (pin "P8") (pinfunction "DAT1_P8") (pintype "bidirectional"))
    )
    (net (code "65") (name "unconnected-(J4-DAT2-PadP1)") (class "Default")
      (node (ref "J4") (pin "P1") (pinfunction "DAT2_P1") (pintype "bidirectional"))
    )
    (net (code "66") (name "unconnected-(J4-DETECTION_1-PadS1)") (class "Default")
      (node (ref "J4") (pin "S1") (pinfunction "DETECTION_1_S1") (pintype "bidirectional"))
    )
    (net (code "67") (name "unconnected-(J4-DETECTION_2-PadS2)") (class "Default")
      (node (ref "J4") (pin "S2") (pinfunction "DETECTION_2_S2") (pintype "bidirectional"))
    )
    (net (code "68") (name "unconnected-(U2-NC-Pad22)") (class "Default")
      (node (ref "U2") (pin "22") (pinfunction "NC_22") (pintype "no_connect"))
    )
    (net (code "69") (name "unconnected-(U4-~{ALERT}-Pad5)") (class "Default")
      (node (ref "U4") (pin "5") (pinfunction "~{ALERT}_5") (pintype "output"))
    )
  )
)
